# ZYNQ_SOC_PWR.net
KiCad netlist of a schematic drawn in Altium Designer
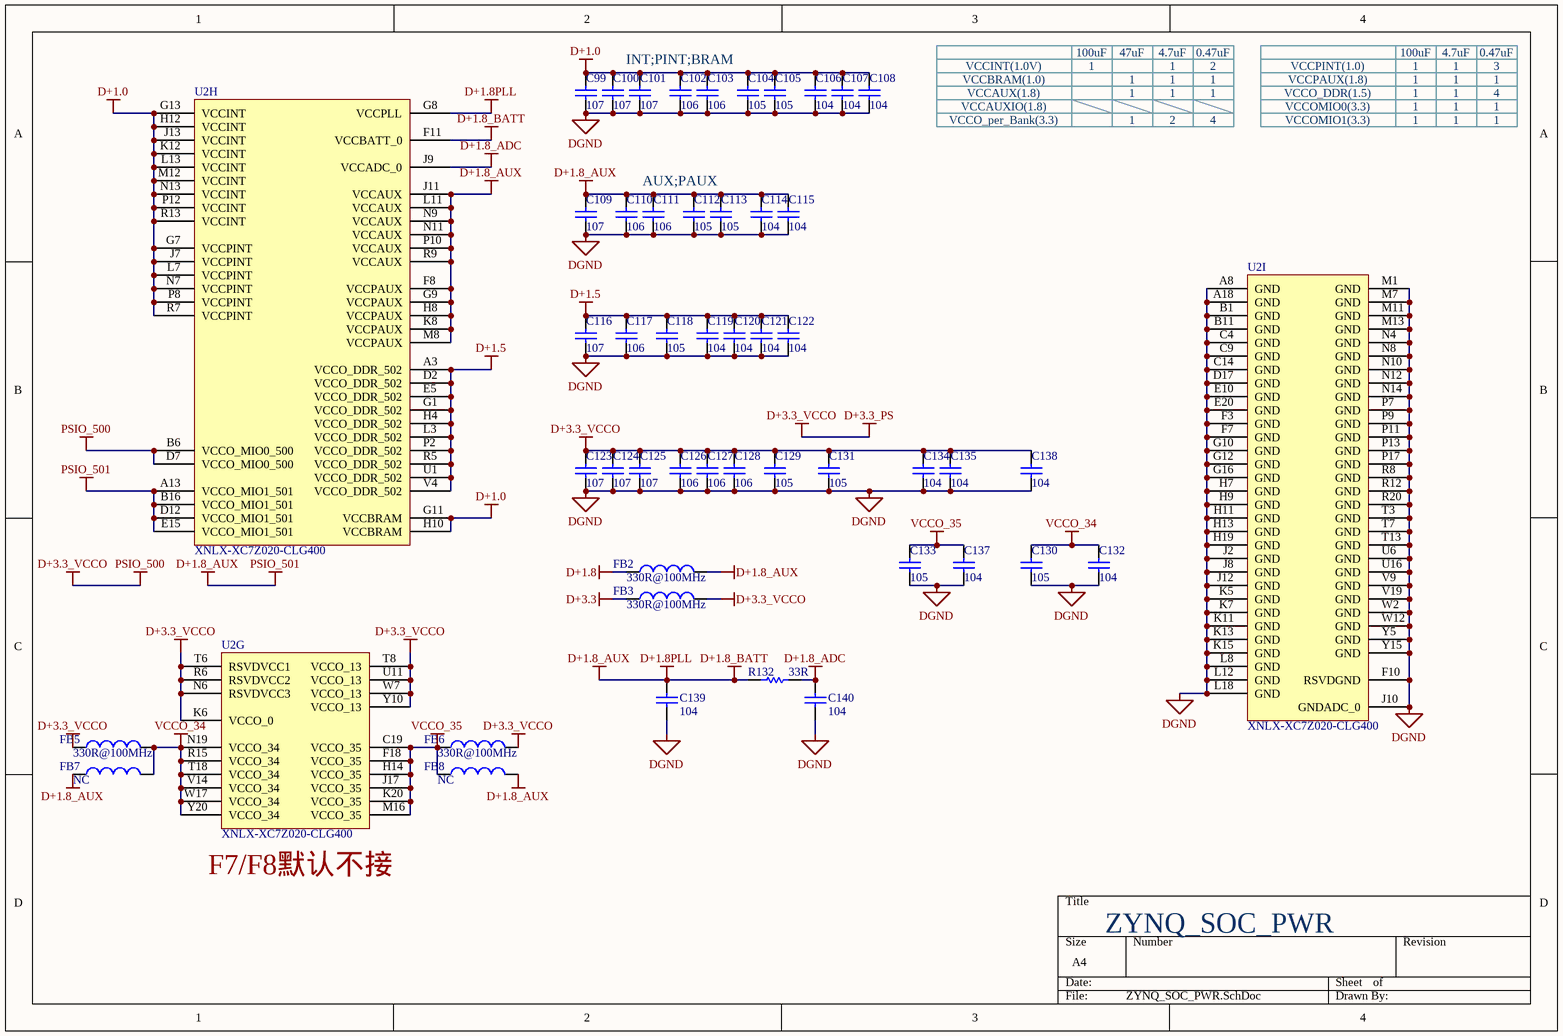
[diagram p0: ZYNQ_SOC_PWR.SchDoc]

(export (version "E")
  (design (tool "Eeschema 10.0.6"))
  (components
    (comp (ref "C99")
      (value "107")
      (footprint "C 1206_L")
      (description "Capacitor")
      (fields (field (name "PUBLISHER") "Altium Limited"))
      (libsource (lib "Miscellaneous Devices") (part "Cap"))
    )
    (comp (ref "C100")
      (value "107")
      (footprint "C 1206_L")
      (description "Capacitor")
      (fields (field (name "PUBLISHER") "Altium Limited"))
      (libsource (lib "Miscellaneous Devices") (part "Cap"))
    )
    (comp (ref "C101")
      (value "107")
      (footprint "C 1206_L")
      (description "Capacitor")
      (fields (field (name "PUBLISHER") "Altium Limited"))
      (libsource (lib "Miscellaneous Devices") (part "Cap"))
    )
    (comp (ref "C102")
      (value "106")
      (footprint "C 0603_L")
      (description "Capacitor")
      (fields (field (name "PUBLISHER") "Altium Limited"))
      (libsource (lib "Miscellaneous Devices") (part "Cap"))
    )
    (comp (ref "C103")
      (value "106")
      (footprint "C 0603_L")
      (description "Capacitor")
      (fields (field (name "PUBLISHER") "Altium Limited"))
      (libsource (lib "Miscellaneous Devices") (part "Cap"))
    )
    (comp (ref "C104")
      (value "105")
      (footprint "C 0402_LL")
      (description "Capacitor")
      (fields (field (name "PUBLISHER") "Altium Limited"))
      (libsource (lib "Miscellaneous Devices") (part "Cap"))
    )
    (comp (ref "C105")
      (value "105")
      (footprint "C 0402_LL")
      (description "Capacitor")
      (fields (field (name "PUBLISHER") "Altium Limited"))
      (libsource (lib "Miscellaneous Devices") (part "Cap"))
    )
    (comp (ref "C106")
      (value "104")
      (footprint "C 0402_LL")
      (description "Capacitor")
      (fields (field (name "PUBLISHER") "Altium Limited"))
      (libsource (lib "Miscellaneous Devices") (part "Cap"))
    )
    (comp (ref "C107")
      (value "104")
      (footprint "C 0402_LL")
      (description "Capacitor")
      (fields (field (name "PUBLISHER") "Altium Limited"))
      (libsource (lib "Miscellaneous Devices") (part "Cap"))
    )
    (comp (ref "C108")
      (value "104")
      (footprint "C 0402_LL")
      (description "Capacitor")
      (fields (field (name "PUBLISHER") "Altium Limited"))
      (libsource (lib "Miscellaneous Devices") (part "Cap"))
    )
    (comp (ref "C109")
      (value "107")
      (footprint "C 1206_L")
      (description "Capacitor")
      (fields (field (name "PUBLISHER") "Altium Limited"))
      (libsource (lib "Miscellaneous Devices") (part "Cap"))
    )
    (comp (ref "C110")
      (value "106")
      (footprint "C 0603_L")
      (description "Capacitor")
      (fields (field (name "PUBLISHER") "Altium Limited"))
      (libsource (lib "Miscellaneous Devices") (part "Cap"))
    )
    (comp (ref "C111")
      (value "106")
      (footprint "C 0603_L")
      (description "Capacitor")
      (fields (field (name "PUBLISHER") "Altium Limited"))
      (libsource (lib "Miscellaneous Devices") (part "Cap"))
    )
    (comp (ref "C112")
      (value "105")
      (footprint "C 0402_LL")
      (description "Capacitor")
      (fields (field (name "PUBLISHER") "Altium Limited"))
      (libsource (lib "Miscellaneous Devices") (part "Cap"))
    )
    (comp (ref "C113")
      (value "105")
      (footprint "C 0402_LL")
      (description "Capacitor")
      (fields (field (name "PUBLISHER") "Altium Limited"))
      (libsource (lib "Miscellaneous Devices") (part "Cap"))
    )
    (comp (ref "C114")
      (value "104")
      (footprint "C 0402_LL")
      (description "Capacitor")
      (fields (field (name "PUBLISHER") "Altium Limited"))
      (libsource (lib "Miscellaneous Devices") (part "Cap"))
    )
    (comp (ref "C115")
      (value "104")
      (footprint "C 0402_LL")
      (description "Capacitor")
      (fields (field (name "PUBLISHER") "Altium Limited"))
      (libsource (lib "Miscellaneous Devices") (part "Cap"))
    )
    (comp (ref "C116")
      (value "107")
      (footprint "C 1206_L")
      (description "Capacitor")
      (fields (field (name "PUBLISHER") "Altium Limited"))
      (libsource (lib "Miscellaneous Devices") (part "Cap"))
    )
    (comp (ref "C117")
      (value "106")
      (footprint "C 0603_L")
      (description "Capacitor")
      (fields (field (name "PUBLISHER") "Altium Limited"))
      (libsource (lib "Miscellaneous Devices") (part "Cap"))
    )
    (comp (ref "C118")
      (value "105")
      (footprint "C 0402_LL")
      (description "Capacitor")
      (fields (field (name "PUBLISHER") "Altium Limited"))
      (libsource (lib "Miscellaneous Devices") (part "Cap"))
    )
    (comp (ref "C119")
      (value "104")
      (footprint "C 0402_LL")
      (description "Capacitor")
      (fields (field (name "PUBLISHER") "Altium Limited"))
      (libsource (lib "Miscellaneous Devices") (part "Cap"))
    )
    (comp (ref "C120")
      (value "104")
      (footprint "C 0402_LL")
      (description "Capacitor")
      (fields (field (name "PUBLISHER") "Altium Limited"))
      (libsource (lib "Miscellaneous Devices") (part "Cap"))
    )
    (comp (ref "C121")
      (value "104")
      (footprint "C 0402_LL")
      (description "Capacitor")
      (fields (field (name "PUBLISHER") "Altium Limited"))
      (libsource (lib "Miscellaneous Devices") (part "Cap"))
    )
    (comp (ref "C122")
      (value "104")
      (footprint "C 0402_LL")
      (description "Capacitor")
      (fields (field (name "PUBLISHER") "Altium Limited"))
      (libsource (lib "Miscellaneous Devices") (part "Cap"))
    )
    (comp (ref "C123")
      (value "107")
      (footprint "C 1206_L")
      (description "Capacitor")
      (fields (field (name "PUBLISHER") "Altium Limited"))
      (libsource (lib "Miscellaneous Devices") (part "Cap"))
    )
    (comp (ref "C124")
      (value "107")
      (footprint "C 1206_L")
      (description "Capacitor")
      (fields (field (name "PUBLISHER") "Altium Limited"))
      (libsource (lib "Miscellaneous Devices") (part "Cap"))
    )
    (comp (ref "C125")
      (value "107")
      (footprint "C 1206_L")
      (description "Capacitor")
      (fields (field (name "PUBLISHER") "Altium Limited"))
      (libsource (lib "Miscellaneous Devices") (part "Cap"))
    )
    (comp (ref "C126")
      (value "106")
      (footprint "C 0603_L")
      (description "Capacitor")
      (fields (field (name "PUBLISHER") "Altium Limited"))
      (libsource (lib "Miscellaneous Devices") (part "Cap"))
    )
    (comp (ref "C127")
      (value "106")
      (footprint "C 0603_L")
      (description "Capacitor")
      (fields (field (name "PUBLISHER") "Altium Limited"))
      (libsource (lib "Miscellaneous Devices") (part "Cap"))
    )
    (comp (ref "C128")
      (value "106")
      (footprint "C 0603_L")
      (description "Capacitor")
      (fields (field (name "PUBLISHER") "Altium Limited"))
      (libsource (lib "Miscellaneous Devices") (part "Cap"))
    )
    (comp (ref "C129")
      (value "105")
      (footprint "C 0402_LL")
      (description "Capacitor")
      (fields (field (name "PUBLISHER") "Altium Limited"))
      (libsource (lib "Miscellaneous Devices") (part "Cap"))
    )
    (comp (ref "C130")
      (value "105")
      (footprint "C 0402_LL")
      (description "Capacitor")
      (fields (field (name "PUBLISHER") "Altium Limited"))
      (libsource (lib "Miscellaneous Devices") (part "Cap"))
    )
    (comp (ref "C131")
      (value "105")
      (footprint "C 0402_LL")
      (description "Capacitor")
      (fields (field (name "PUBLISHER") "Altium Limited"))
      (libsource (lib "Miscellaneous Devices") (part "Cap"))
    )
    (comp (ref "C132")
      (value "104")
      (footprint "C 0402_LL")
      (description "Capacitor")
      (fields (field (name "PUBLISHER") "Altium Limited"))
      (libsource (lib "Miscellaneous Devices") (part "Cap"))
    )
    (comp (ref "C133")
      (value "105")
      (footprint "C 0402_LL")
      (description "Capacitor")
      (fields (field (name "PUBLISHER") "Altium Limited"))
      (libsource (lib "Miscellaneous Devices") (part "Cap"))
    )
    (comp (ref "C134")
      (value "104")
      (footprint "C 0402_LL")
      (description "Capacitor")
      (fields (field (name "PUBLISHER") "Altium Limited"))
      (libsource (lib "Miscellaneous Devices") (part "Cap"))
    )
    (comp (ref "C135")
      (value "104")
      (footprint "C 0402_LL")
      (description "Capacitor")
      (fields (field (name "PUBLISHER") "Altium Limited"))
      (libsource (lib "Miscellaneous Devices") (part "Cap"))
    )
    (comp (ref "C137")
      (value "104")
      (footprint "C 0402_LL")
      (description "Capacitor")
      (fields (field (name "PUBLISHER") "Altium Limited"))
      (libsource (lib "Miscellaneous Devices") (part "Cap"))
    )
    (comp (ref "C138")
      (value "104")
      (footprint "C 0402_LL")
      (description "Capacitor")
      (fields (field (name "PUBLISHER") "Altium Limited"))
      (libsource (lib "Miscellaneous Devices") (part "Cap"))
    )
    (comp (ref "C139")
      (value "104")
      (footprint "C 0402_LL")
      (description "Capacitor")
      (fields (field (name "PUBLISHER") "Altium Limited"))
      (libsource (lib "Miscellaneous Devices") (part "Cap"))
    )
    (comp (ref "C140")
      (value "104")
      (footprint "C 0402_LL")
      (description "Capacitor")
      (fields (field (name "PUBLISHER") "Altium Limited"))
      (libsource (lib "Miscellaneous Devices") (part "Cap"))
    )
    (comp (ref "FB2")
      (value "330R@100MHz")
      (footprint "L 0805")
      (description "Inductor")
      (fields (field (name "Comment") "Ferrite Bead") (field (name "PUBLISHER") "Altium Limited"))
      (libsource (lib "Miscellaneous Devices") (part "Inductor"))
    )
    (comp (ref "FB3")
      (value "330R@100MHz")
      (footprint "L 0805")
      (description "Inductor")
      (fields (field (name "Comment") "Ferrite Bead") (field (name "PUBLISHER") "Altium Limited"))
      (libsource (lib "Miscellaneous Devices") (part "Inductor"))
    )
    (comp (ref "FB5")
      (value "330R@100MHz")
      (footprint "L 0805")
      (description "Inductor")
      (fields (field (name "Comment") "Ferrite Bead") (field (name "PUBLISHER") "Altium Limited"))
      (libsource (lib "Miscellaneous Devices") (part "Inductor"))
    )
    (comp (ref "FB6")
      (value "330R@100MHz")
      (footprint "L 0805")
      (description "Inductor")
      (fields (field (name "Comment") "Ferrite Bead") (field (name "PUBLISHER") "Altium Limited"))
      (libsource (lib "Miscellaneous Devices") (part "Inductor"))
    )
    (comp (ref "FB7")
      (value "NC")
      (footprint "L 0805")
      (description "Inductor")
      (fields (field (name "Comment") "Ferrite Bead") (field (name "PUBLISHER") "Altium Limited"))
      (libsource (lib "Miscellaneous Devices") (part "Inductor"))
    )
    (comp (ref "FB8")
      (value "NC")
      (footprint "L 0805")
      (description "Inductor")
      (fields (field (name "Comment") "Ferrite Bead") (field (name "PUBLISHER") "Altium Limited"))
      (libsource (lib "Miscellaneous Devices") (part "Inductor"))
    )
    (comp (ref "R132")
      (value "33R")
      (footprint "R 0402_L")
      (description "Resistor")
      (fields (field (name "PUBLISHER") "Altium Limited"))
      (libsource (lib "Miscellaneous Devices") (part "Res1"))
    )
    (comp (ref "U2")
      (value "XNLX-XC7Z020-CLG400")
      (footprint "BGA400")
      (description "xilinx双核A9处理器与FPGA集成的SoC")
      (fields (field (name "MANUFACTURER") "xilinx"))
      (libsource (lib "龙井V1") (part "XNLX-XC7Z020-CLG400"))
    )
  )
  (nets
    (net (code "1") (name "D+1.0") (class "Default")
      (node (ref "C100") (pin "2") (pinfunction "2_2") (pintype "passive"))
      (node (ref "C101") (pin "2") (pinfunction "2_2") (pintype "passive"))
      (node (ref "C102") (pin "2") (pinfunction "2_2") (pintype "passive"))
      (node (ref "C103") (pin "2") (pinfunction "2_2") (pintype "passive"))
      (node (ref "C104") (pin "2") (pinfunction "2_2") (pintype "passive"))
      (node (ref "C105") (pin "2") (pinfunction "2_2") (pintype "passive"))
      (node (ref "C106") (pin "2") (pinfunction "2_2") (pintype "passive"))
      (node (ref "C107") (pin "2") (pinfunction "2_2") (pintype "passive"))
      (node (ref "C108") (pin "2") (pinfunction "2_2") (pintype "passive"))
      (node (ref "C99") (pin "2") (pinfunction "2_2") (pintype "passive"))
      (node (ref "U2") (pin "G11") (pinfunction "VCCBRAM_G11") (pintype "power_in"))
      (node (ref "U2") (pin "G13") (pinfunction "VCCINT_G13") (pintype "power_in"))
      (node (ref "U2") (pin "G7") (pinfunction "VCCPINT_G7") (pintype "power_in"))
      (node (ref "U2") (pin "H10") (pinfunction "VCCBRAM_H10") (pintype "power_in"))
      (node (ref "U2") (pin "H12") (pinfunction "VCCINT_H12") (pintype "power_in"))
      (node (ref "U2") (pin "J13") (pinfunction "VCCINT_J13") (pintype "power_in"))
      (node (ref "U2") (pin "J7") (pinfunction "VCCPINT_J7") (pintype "power_in"))
      (node (ref "U2") (pin "K12") (pinfunction "VCCINT_K12") (pintype "power_in"))
      (node (ref "U2") (pin "L13") (pinfunction "VCCINT_L13") (pintype "power_in"))
      (node (ref "U2") (pin "L7") (pinfunction "VCCPINT_L7") (pintype "power_in"))
      (node (ref "U2") (pin "M12") (pinfunction "VCCINT_M12") (pintype "power_in"))
      (node (ref "U2") (pin "N13") (pinfunction "VCCINT_N13") (pintype "power_in"))
      (node (ref "U2") (pin "N7") (pinfunction "VCCPINT_N7") (pintype "power_in"))
      (node (ref "U2") (pin "P12") (pinfunction "VCCINT_P12") (pintype "power_in"))
      (node (ref "U2") (pin "P8") (pinfunction "VCCPINT_P8") (pintype "power_in"))
      (node (ref "U2") (pin "R13") (pinfunction "VCCINT_R13") (pintype "power_in"))
      (node (ref "U2") (pin "R7") (pinfunction "VCCPINT_R7") (pintype "power_in"))
    )
    (net (code "2") (name "D+1.5") (class "Default")
      (node (ref "C116") (pin "2") (pinfunction "2_2") (pintype "passive"))
      (node (ref "C117") (pin "2") (pinfunction "2_2") (pintype "passive"))
      (node (ref "C118") (pin "2") (pinfunction "2_2") (pintype "passive"))
      (node (ref "C119") (pin "2") (pinfunction "2_2") (pintype "passive"))
      (node (ref "C120") (pin "2") (pinfunction "2_2") (pintype "passive"))
      (node (ref "C121") (pin "2") (pinfunction "2_2") (pintype "passive"))
      (node (ref "C122") (pin "2") (pinfunction "2_2") (pintype "passive"))
      (node (ref "U2") (pin "A3") (pinfunction "VCCO_DDR_502_A3") (pintype "power_in"))
      (node (ref "U2") (pin "D2") (pinfunction "VCCO_DDR_502_D2") (pintype "power_in"))
      (node (ref "U2") (pin "E5") (pinfunction "VCCO_DDR_502_E5") (pintype "power_in"))
      (node (ref "U2") (pin "G1") (pinfunction "VCCO_DDR_502_G1") (pintype "power_in"))
      (node (ref "U2") (pin "H4") (pinfunction "VCCO_DDR_502_H4") (pintype "power_in"))
      (node (ref "U2") (pin "L3") (pinfunction "VCCO_DDR_502_L3") (pintype "power_in"))
      (node (ref "U2") (pin "P2") (pinfunction "VCCO_DDR_502_P2") (pintype "power_in"))
      (node (ref "U2") (pin "R5") (pinfunction "VCCO_DDR_502_R5") (pintype "power_in"))
      (node (ref "U2") (pin "U1") (pinfunction "VCCO_DDR_502_U1") (pintype "power_in"))
      (node (ref "U2") (pin "V4") (pinfunction "VCCO_DDR_502_V4") (pintype "power_in"))
    )
    (net (code "3") (name "D+1.8") (class "Default")
      (node (ref "FB2") (pin "1") (pinfunction "1_1") (pintype "passive"))
    )
    (net (code "4") (name "D+1.8PLL") (class "Default")
      (node (ref "C109") (pin "2") (pinfunction "2_2") (pintype "passive"))
      (node (ref "C110") (pin "2") (pinfunction "2_2") (pintype "passive"))
      (node (ref "C111") (pin "2") (pinfunction "2_2") (pintype "passive"))
      (node (ref "C112") (pin "2") (pinfunction "2_2") (pintype "passive"))
      (node (ref "C113") (pin "2") (pinfunction "2_2") (pintype "passive"))
      (node (ref "C114") (pin "2") (pinfunction "2_2") (pintype "passive"))
      (node (ref "C115") (pin "2") (pinfunction "2_2") (pintype "passive"))
      (node (ref "C139") (pin "2") (pinfunction "2_2") (pintype "passive"))
      (node (ref "FB2") (pin "2") (pinfunction "2_2") (pintype "passive"))
      (node (ref "FB7") (pin "1") (pinfunction "1_1") (pintype "passive"))
      (node (ref "FB8") (pin "2") (pinfunction "2_2") (pintype "passive"))
      (node (ref "R132") (pin "2") (pinfunction "2_2") (pintype "passive"))
      (node (ref "U2") (pin "A13") (pinfunction "VCCO_MIO1_501_A13") (pintype "power_in"))
      (node (ref "U2") (pin "B16") (pinfunction "VCCO_MIO1_501_B16") (pintype "power_in"))
      (node (ref "U2") (pin "D12") (pinfunction "VCCO_MIO1_501_D12") (pintype "power_in"))
      (node (ref "U2") (pin "E15") (pinfunction "VCCO_MIO1_501_E15") (pintype "power_in"))
      (node (ref "U2") (pin "F11") (pinfunction "VCCBATT_0_F11") (pintype "power_in"))
      (node (ref "U2") (pin "F8") (pinfunction "VCCPAUX_F8") (pintype "power_in"))
      (node (ref "U2") (pin "G8") (pinfunction "VCCPLL_G8") (pintype "power_in"))
      (node (ref "U2") (pin "G9") (pinfunction "VCCPAUX_G9") (pintype "power_in"))
      (node (ref "U2") (pin "H8") (pinfunction "VCCPAUX_H8") (pintype "power_in"))
      (node (ref "U2") (pin "J11") (pinfunction "VCCAUX_J11") (pintype "power_in"))
      (node (ref "U2") (pin "K8") (pinfunction "VCCPAUX_K8") (pintype "power_in"))
      (node (ref "U2") (pin "L11") (pinfunction "VCCAUX_L11") (pintype "power_in"))
      (node (ref "U2") (pin "M8") (pinfunction "VCCPAUX_M8") (pintype "power_in"))
      (node (ref "U2") (pin "N11") (pinfunction "VCCAUX_N11") (pintype "power_in"))
      (node (ref "U2") (pin "N9") (pinfunction "VCCAUX_N9") (pintype "power_in"))
      (node (ref "U2") (pin "P10") (pinfunction "VCCAUX_P10") (pintype "power_in"))
      (node (ref "U2") (pin "R9") (pinfunction "VCCAUX_R9") (pintype "power_in"))
    )
    (net (code "5") (name "D+1.8_ADC") (class "Default")
      (node (ref "C140") (pin "2") (pinfunction "2_2") (pintype "passive"))
      (node (ref "R132") (pin "1") (pinfunction "1_1") (pintype "passive"))
      (node (ref "U2") (pin "J9") (pinfunction "VCCADC_0_J9") (pintype "power_in"))
    )
    (net (code "6") (name "D+3.3") (class "Default")
      (node (ref "FB3") (pin "1") (pinfunction "1_1") (pintype "passive"))
    )
    (net (code "7") (name "D+3.3_PS") (class "Default")
      (node (ref "C123") (pin "2") (pinfunction "2_2") (pintype "passive"))
      (node (ref "C124") (pin "2") (pinfunction "2_2") (pintype "passive"))
      (node (ref "C125") (pin "2") (pinfunction "2_2") (pintype "passive"))
      (node (ref "C126") (pin "2") (pinfunction "2_2") (pintype "passive"))
      (node (ref "C127") (pin "2") (pinfunction "2_2") (pintype "passive"))
      (node (ref "C128") (pin "2") (pinfunction "2_2") (pintype "passive"))
      (node (ref "C129") (pin "2") (pinfunction "2_2") (pintype "passive"))
      (node (ref "C131") (pin "2") (pinfunction "2_2") (pintype "passive"))
      (node (ref "C134") (pin "2") (pinfunction "2_2") (pintype "passive"))
      (node (ref "C135") (pin "2") (pinfunction "2_2") (pintype "passive"))
      (node (ref "C138") (pin "2") (pinfunction "2_2") (pintype "passive"))
      (node (ref "FB3") (pin "2") (pinfunction "2_2") (pintype "passive"))
      (node (ref "FB5") (pin "1") (pinfunction "1_1") (pintype "passive"))
      (node (ref "FB6") (pin "2") (pinfunction "2_2") (pintype "passive"))
      (node (ref "U2") (pin "B6") (pinfunction "VCCO_MIO0_500_B6") (pintype "power_in"))
      (node (ref "U2") (pin "D7") (pinfunction "VCCO_MIO0_500_D7") (pintype "power_in"))
      (node (ref "U2") (pin "K6") (pinfunction "VCCO_0_K6") (pintype "power_in"))
      (node (ref "U2") (pin "N6") (pinfunction "RSVDVCC3_N6") (pintype "power_in"))
      (node (ref "U2") (pin "R6") (pinfunction "RSVDVCC2_R6") (pintype "power_in"))
      (node (ref "U2") (pin "T6") (pinfunction "RSVDVCC1_T6") (pintype "power_in"))
      (node (ref "U2") (pin "T8") (pinfunction "VCCO_13_T8") (pintype "power_in"))
      (node (ref "U2") (pin "U11") (pinfunction "VCCO_13_U11") (pintype "power_in"))
      (node (ref "U2") (pin "W7") (pinfunction "VCCO_13_W7") (pintype "power_in"))
      (node (ref "U2") (pin "Y10") (pinfunction "VCCO_13_Y10") (pintype "power_in"))
    )
    (net (code "8") (name "DGND") (class "Default")
      (node (ref "C100") (pin "1") (pinfunction "1_1") (pintype "passive"))
      (node (ref "C101") (pin "1") (pinfunction "1_1") (pintype "passive"))
      (node (ref "C102") (pin "1") (pinfunction "1_1") (pintype "passive"))
      (node (ref "C103") (pin "1") (pinfunction "1_1") (pintype "passive"))
      (node (ref "C104") (pin "1") (pinfunction "1_1") (pintype "passive"))
      (node (ref "C105") (pin "1") (pinfunction "1_1") (pintype "passive"))
      (node (ref "C106") (pin "1") (pinfunction "1_1") (pintype "passive"))
      (node (ref "C107") (pin "1") (pinfunction "1_1") (pintype "passive"))
      (node (ref "C108") (pin "1") (pinfunction "1_1") (pintype "passive"))
      (node (ref "C109") (pin "1") (pinfunction "1_1") (pintype "passive"))
      (node (ref "C110") (pin "1") (pinfunction "1_1") (pintype "passive"))
      (node (ref "C111") (pin "1") (pinfunction "1_1") (pintype "passive"))
      (node (ref "C112") (pin "1") (pinfunction "1_1") (pintype "passive"))
      (node (ref "C113") (pin "1") (pinfunction "1_1") (pintype "passive"))
      (node (ref "C114") (pin "1") (pinfunction "1_1") (pintype "passive"))
      (node (ref "C115") (pin "1") (pinfunction "1_1") (pintype "passive"))
      (node (ref "C116") (pin "1") (pinfunction "1_1") (pintype "passive"))
      (node (ref "C117") (pin "1") (pinfunction "1_1") (pintype "passive"))
      (node (ref "C118") (pin "1") (pinfunction "1_1") (pintype "passive"))
      (node (ref "C119") (pin "1") (pinfunction "1_1") (pintype "passive"))
      (node (ref "C120") (pin "1") (pinfunction "1_1") (pintype "passive"))
      (node (ref "C121") (pin "1") (pinfunction "1_1") (pintype "passive"))
      (node (ref "C122") (pin "1") (pinfunction "1_1") (pintype "passive"))
      (node (ref "C123") (pin "1") (pinfunction "1_1") (pintype "passive"))
      (node (ref "C124") (pin "1") (pinfunction "1_1") (pintype "passive"))
      (node (ref "C125") (pin "1") (pinfunction "1_1") (pintype "passive"))
      (node (ref "C126") (pin "1") (pinfunction "1_1") (pintype "passive"))
      (node (ref "C127") (pin "1") (pinfunction "1_1") (pintype "passive"))
      (node (ref "C128") (pin "1") (pinfunction "1_1") (pintype "passive"))
      (node (ref "C129") (pin "1") (pinfunction "1_1") (pintype "passive"))
      (node (ref "C130") (pin "1") (pinfunction "1_1") (pintype "passive"))
      (node (ref "C131") (pin "1") (pinfunction "1_1") (pintype "passive"))
      (node (ref "C132") (pin "1") (pinfunction "1_1") (pintype "passive"))
      (node (ref "C133") (pin "1") (pinfunction "1_1") (pintype "passive"))
      (node (ref "C134") (pin "1") (pinfunction "1_1") (pintype "passive"))
      (node (ref "C135") (pin "1") (pinfunction "1_1") (pintype "passive"))
      (node (ref "C137") (pin "1") (pinfunction "1_1") (pintype "passive"))
      (node (ref "C138") (pin "1") (pinfunction "1_1") (pintype "passive"))
      (node (ref "C139") (pin "1") (pinfunction "1_1") (pintype "passive"))
      (node (ref "C140") (pin "1") (pinfunction "1_1") (pintype "passive"))
      (node (ref "C99") (pin "1") (pinfunction "1_1") (pintype "passive"))
      (node (ref "U2") (pin "A18") (pinfunction "GND_A18") (pintype "power_in"))
      (node (ref "U2") (pin "A8") (pinfunction "GND_A8") (pintype "power_in"))
      (node (ref "U2") (pin "B1") (pinfunction "GND_B1") (pintype "power_in"))
      (node (ref "U2") (pin "B11") (pinfunction "GND_B11") (pintype "power_in"))
      (node (ref "U2") (pin "C14") (pinfunction "GND_C14") (pintype "power_in"))
      (node (ref "U2") (pin "C4") (pinfunction "GND_C4") (pintype "power_in"))
      (node (ref "U2") (pin "C9") (pinfunction "GND_C9") (pintype "power_in"))
      (node (ref "U2") (pin "D17") (pinfunction "GND_D17") (pintype "power_in"))
      (node (ref "U2") (pin "E10") (pinfunction "GND_E10") (pintype "power_in"))
      (node (ref "U2") (pin "E20") (pinfunction "GND_E20") (pintype "power_in"))
      (node (ref "U2") (pin "F10") (pinfunction "RSVDGND_F10") (pintype "power_in"))
      (node (ref "U2") (pin "F3") (pinfunction "GND_F3") (pintype "power_in"))
      (node (ref "U2") (pin "F7") (pinfunction "GND_F7") (pintype "power_in"))
      (node (ref "U2") (pin "G10") (pinfunction "GND_G10") (pintype "power_in"))
      (node (ref "U2") (pin "G12") (pinfunction "GND_G12") (pintype "power_in"))
      (node (ref "U2") (pin "G16") (pinfunction "GND_G16") (pintype "power_in"))
      (node (ref "U2") (pin "H11") (pinfunction "GND_H11") (pintype "power_in"))
      (node (ref "U2") (pin "H13") (pinfunction "GND_H13") (pintype "power_in"))
      (node (ref "U2") (pin "H19") (pinfunction "GND_H19") (pintype "power_in"))
      (node (ref "U2") (pin "H7") (pinfunction "GND_H7") (pintype "power_in"))
      (node (ref "U2") (pin "H9") (pinfunction "GND_H9") (pintype "power_in"))
      (node (ref "U2") (pin "J10") (pinfunction "GNDADC_0_J10") (pintype "power_in"))
      (node (ref "U2") (pin "J12") (pinfunction "GND_J12") (pintype "power_in"))
      (node (ref "U2") (pin "J2") (pinfunction "GND_J2") (pintype "power_in"))
      (node (ref "U2") (pin "J8") (pinfunction "GND_J8") (pintype "power_in"))
      (node (ref "U2") (pin "K11") (pinfunction "GND_K11") (pintype "power_in"))
      (node (ref "U2") (pin "K13") (pinfunction "GND_K13") (pintype "power_in"))
      (node (ref "U2") (pin "K15") (pinfunction "GND_K15") (pintype "power_in"))
      (node (ref "U2") (pin "K5") (pinfunction "GND_K5") (pintype "power_in"))
      (node (ref "U2") (pin "K7") (pinfunction "GND_K7") (pintype "power_in"))
      (node (ref "U2") (pin "L12") (pinfunction "GND_L12") (pintype "power_in"))
      (node (ref "U2") (pin "L18") (pinfunction "GND_L18") (pintype "power_in"))
      (node (ref "U2") (pin "L8") (pinfunction "GND_L8") (pintype "power_in"))
      (node (ref "U2") (pin "M1") (pinfunction "GND_M1") (pintype "power_in"))
      (node (ref "U2") (pin "M11") (pinfunction "GND_M11") (pintype "power_in"))
      (node (ref "U2") (pin "M13") (pinfunction "GND_M13") (pintype "power_in"))
      (node (ref "U2") (pin "M7") (pinfunction "GND_M7") (pintype "power_in"))
      (node (ref "U2") (pin "N10") (pinfunction "GND_N10") (pintype "power_in"))
      (node (ref "U2") (pin "N12") (pinfunction "GND_N12") (pintype "power_in"))
      (node (ref "U2") (pin "N14") (pinfunction "GND_N14") (pintype "power_in"))
      (node (ref "U2") (pin "N4") (pinfunction "GND_N4") (pintype "power_in"))
      (node (ref "U2") (pin "N8") (pinfunction "GND_N8") (pintype "power_in"))
      (node (ref "U2") (pin "P11") (pinfunction "GND_P11") (pintype "power_in"))
      (node (ref "U2") (pin "P13") (pinfunction "GND_P13") (pintype "power_in"))
      (node (ref "U2") (pin "P17") (pinfunction "GND_P17") (pintype "power_in"))
      (node (ref "U2") (pin "P7") (pinfunction "GND_P7") (pintype "power_in"))
      (node (ref "U2") (pin "P9") (pinfunction "GND_P9") (pintype "power_in"))
      (node (ref "U2") (pin "R12") (pinfunction "GND_R12") (pintype "power_in"))
      (node (ref "U2") (pin "R20") (pinfunction "GND_R20") (pintype "power_in"))
      (node (ref "U2") (pin "R8") (pinfunction "GND_R8") (pintype "power_in"))
      (node (ref "U2") (pin "T13") (pinfunction "GND_T13") (pintype "power_in"))
      (node (ref "U2") (pin "T3") (pinfunction "GND_T3") (pintype "power_in"))
      (node (ref "U2") (pin "T7") (pinfunction "GND_T7") (pintype "power_in"))
      (node (ref "U2") (pin "U16") (pinfunction "GND_U16") (pintype "power_in"))
      (node (ref "U2") (pin "U6") (pinfunction "GND_U6") (pintype "power_in"))
      (node (ref "U2") (pin "V19") (pinfunction "GND_V19") (pintype "power_in"))
      (node (ref "U2") (pin "V9") (pinfunction "GND_V9") (pintype "power_in"))
      (node (ref "U2") (pin "W12") (pinfunction "GND_W12") (pintype "power_in"))
      (node (ref "U2") (pin "W2") (pinfunction "GND_W2") (pintype "power_in"))
      (node (ref "U2") (pin "Y15") (pinfunction "GND_Y15") (pintype "power_in"))
      (node (ref "U2") (pin "Y5") (pinfunction "GND_Y5") (pintype "power_in"))
    )
    (net (code "9") (name "VCCO_34") (class "Default")
      (node (ref "C130") (pin "2") (pinfunction "2_2") (pintype "passive"))
      (node (ref "C132") (pin "2") (pinfunction "2_2") (pintype "passive"))
      (node (ref "FB5") (pin "2") (pinfunction "2_2") (pintype "passive"))
      (node (ref "FB7") (pin "2") (pinfunction "2_2") (pintype "passive"))
      (node (ref "U2") (pin "N19") (pinfunction "VCCO_34_N19") (pintype "power_in"))
      (node (ref "U2") (pin "R15") (pinfunction "VCCO_34_R15") (pintype "power_in"))
      (node (ref "U2") (pin "T18") (pinfunction "VCCO_34_T18") (pintype "power_in"))
      (node (ref "U2") (pin "V14") (pinfunction "VCCO_34_V14") (pintype "power_in"))
      (node (ref "U2") (pin "W17") (pinfunction "VCCO_34_W17") (pintype "power_in"))
      (node (ref "U2") (pin "Y20") (pinfunction "VCCO_34_Y20") (pintype "power_in"))
    )
    (net (code "10") (name "VCCO_35") (class "Default")
      (node (ref "C133") (pin "2") (pinfunction "2_2") (pintype "passive"))
      (node (ref "C137") (pin "2") (pinfunction "2_2") (pintype "passive"))
      (node (ref "FB6") (pin "1") (pinfunction "1_1") (pintype "passive"))
      (node (ref "FB8") (pin "1") (pinfunction "1_1") (pintype "passive"))
      (node (ref "U2") (pin "C19") (pinfunction "VCCO_35_C19") (pintype "power_in"))
      (node (ref "U2") (pin "F18") (pinfunction "VCCO_35_F18") (pintype "power_in"))
      (node (ref "U2") (pin "H14") (pinfunction "VCCO_35_H14") (pintype "power_in"))
      (node (ref "U2") (pin "J17") (pinfunction "VCCO_35_J17") (pintype "power_in"))
      (node (ref "U2") (pin "K20") (pinfunction "VCCO_35_K20") (pintype "power_in"))
      (node (ref "U2") (pin "M16") (pinfunction "VCCO_35_M16") (pintype "power_in"))
    )
  )
)
